# ProtectionChannelC.net
KiCad netlist of a schematic drawn in Altium Designer
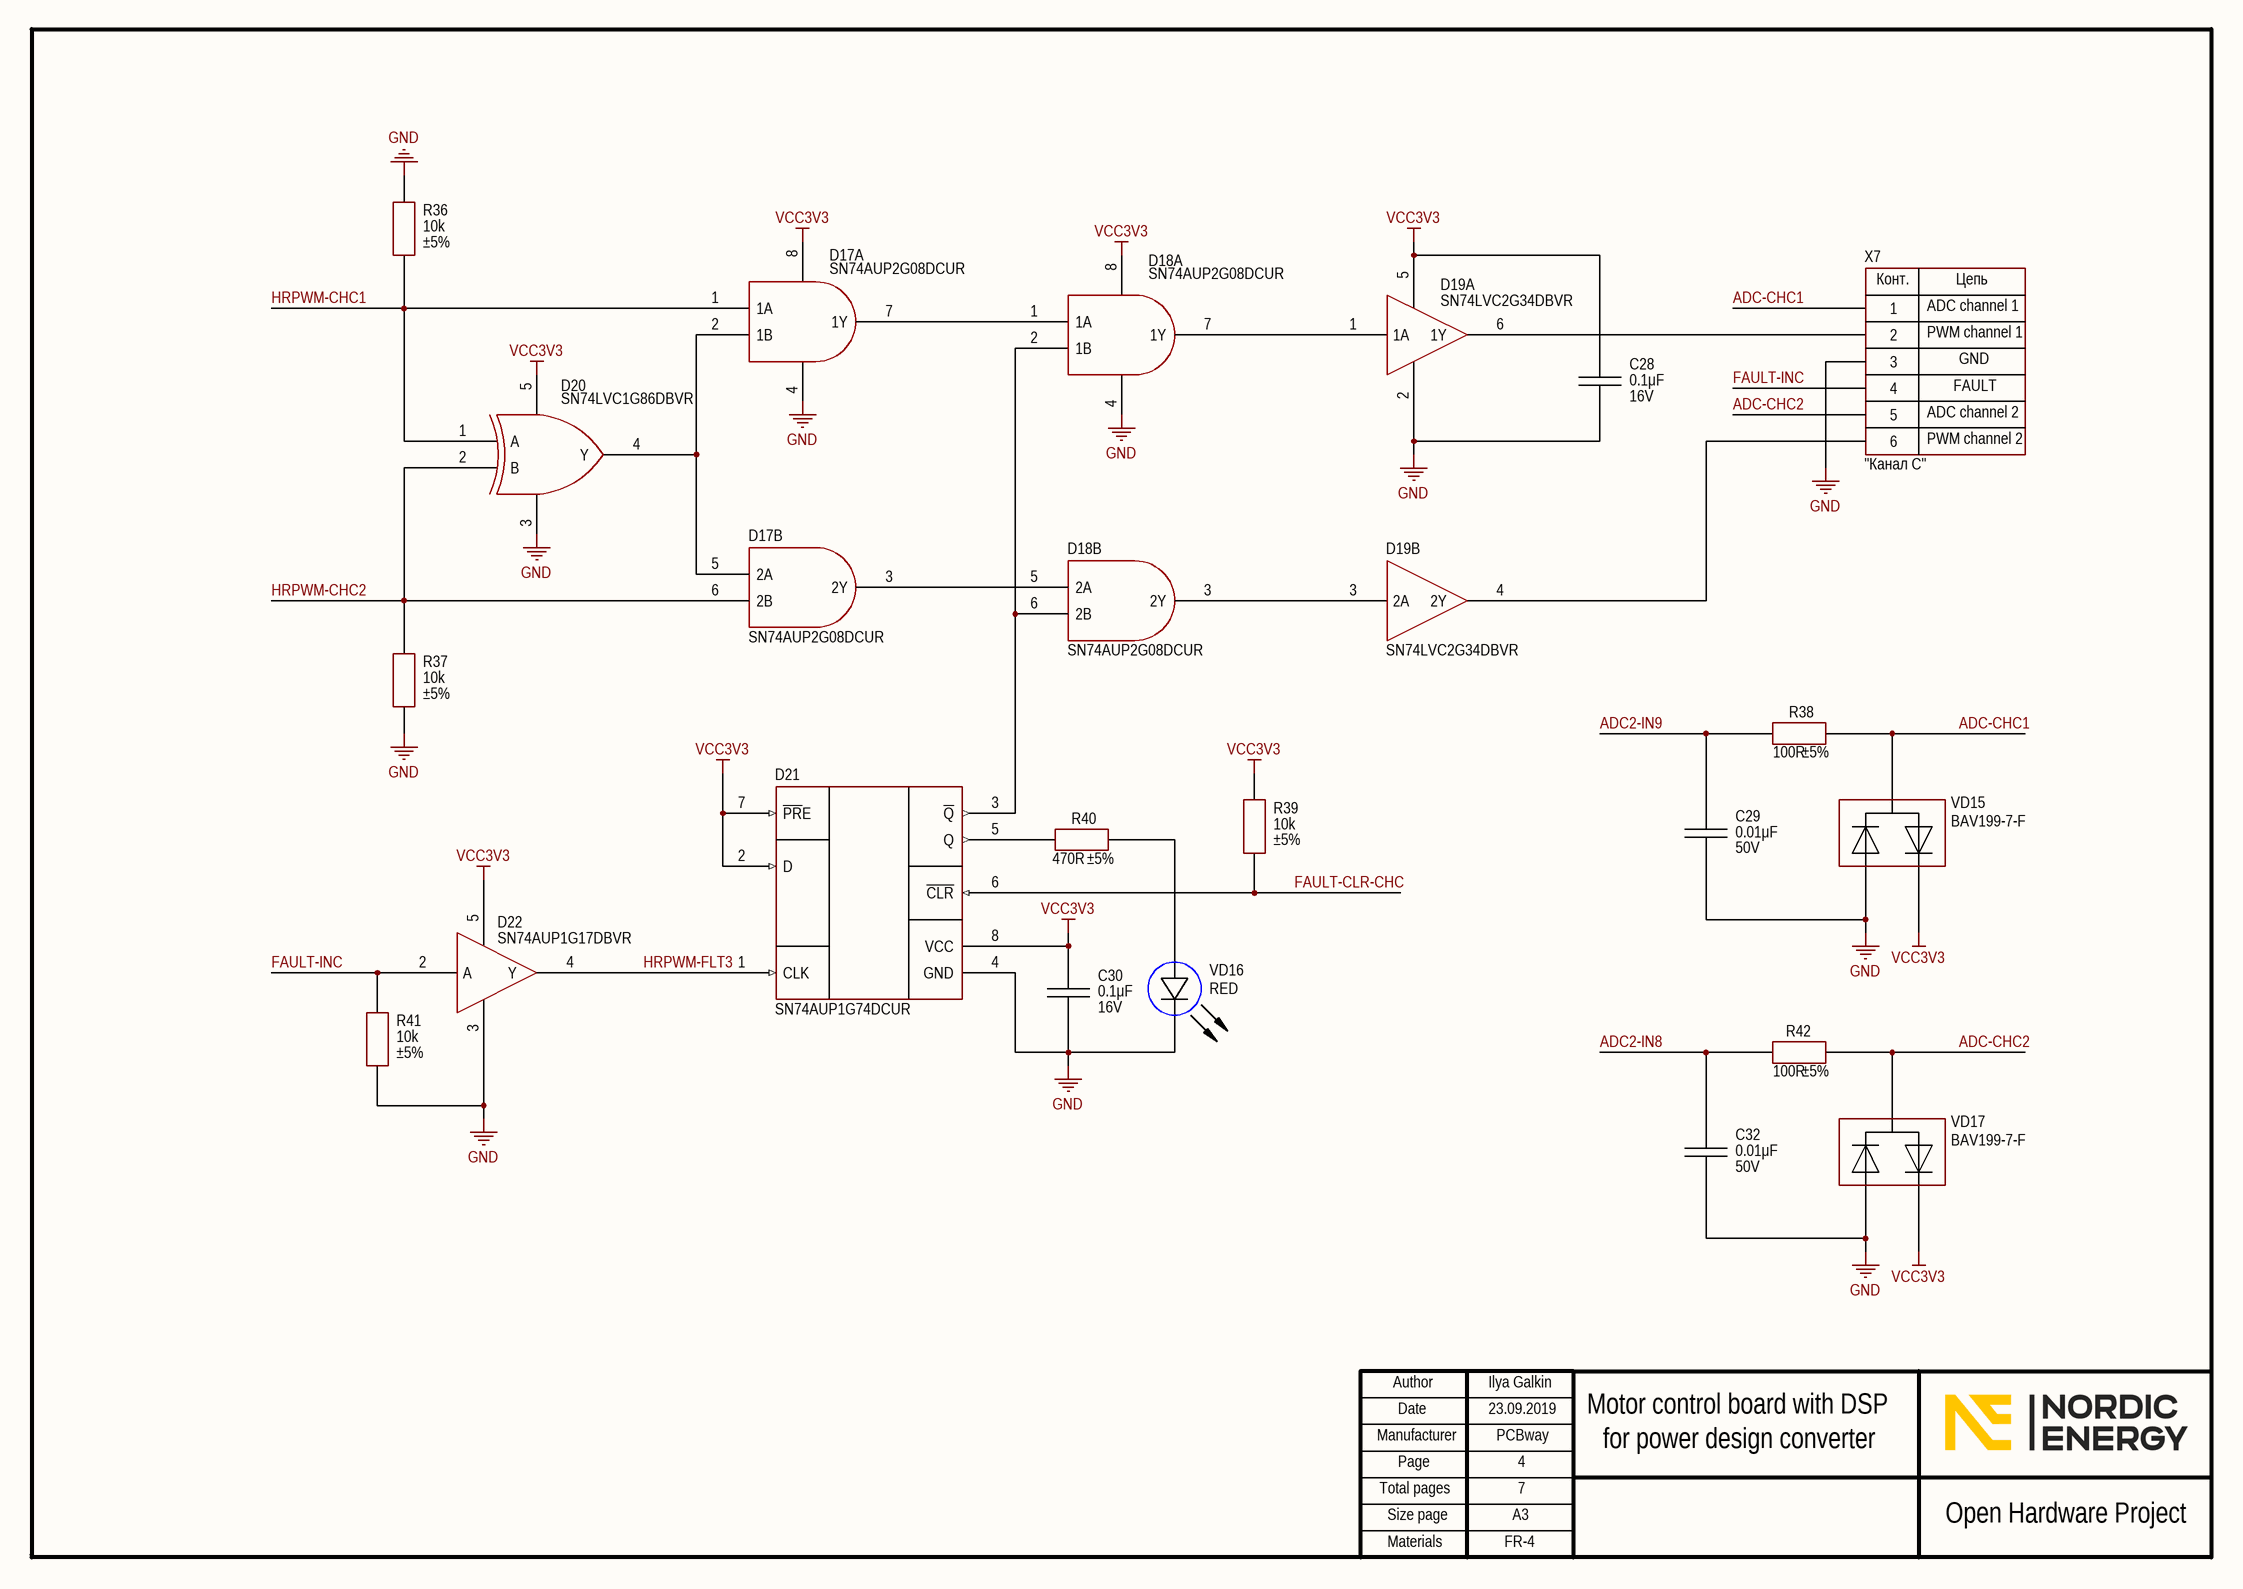
[diagram p0: ProtectionChannelC.SchDoc]

(export (version "E")
  (design (tool "Eeschema 10.0.6"))
  (components
    (comp (ref "C28")
      (value "0.1μF")
      (footprint "CAP: 0805")
      (fields
        (field (name "MANUFACTURER") "Yageo")
        (field (name "PARTNUMBER") "CC0805KRX7R7BB104")
        (field (name "VALUEMANUFACTURERPARTNUMBER") "Ceramic capacitor, 0.1μF, X7R, ±10%, 16V, 0805, -55...+125°C")
        (field (name "VOLTAGE") "16V")
      )
      (libsource (lib "Capacitor") (part "Ceramic_0805"))
    )
    (comp (ref "C29")
      (value "0.01μF")
      (footprint "CAP: 0805")
      (fields
        (field (name "MANUFACTURER") "Yageo")
        (field (name "PARTNUMBER") "CC0805KRX7R9BB103")
        (field (name "VALUEMANUFACTURERPARTNUMBER") "Ceramic capacitor, 0.01μF, X7R, ±10%, 50V, 0805, -55...+125°C")
        (field (name "VOLTAGE") "50V")
      )
      (libsource (lib "Capacitor") (part "Ceramic_0805"))
    )
    (comp (ref "C30")
      (value "0.1μF")
      (footprint "CAP: 0805")
      (fields
        (field (name "MANUFACTURER") "Yageo")
        (field (name "PARTNUMBER") "CC0805KRX7R7BB104")
        (field (name "VALUEMANUFACTURERPARTNUMBER") "Ceramic capacitor, 0.1μF, X7R, ±10%, 16V, 0805, -55...+125°C")
        (field (name "VOLTAGE") "16V")
      )
      (libsource (lib "Capacitor") (part "Ceramic_0805"))
    )
    (comp (ref "C32")
      (value "0.01μF")
      (footprint "CAP: 0805")
      (fields
        (field (name "MANUFACTURER") "Yageo")
        (field (name "PARTNUMBER") "CC0805KRX7R9BB103")
        (field (name "VALUEMANUFACTURERPARTNUMBER") "Ceramic capacitor, 0.01μF, X7R, ±10%, 50V, 0805, -55...+125°C")
        (field (name "VOLTAGE") "50V")
      )
      (libsource (lib "Capacitor") (part "Ceramic_0805"))
    )
    (comp (ref "D17")
      (value "~")
      (footprint "8-VSSOP")
      (description "AND")
      (fields
        (field (name "MANUFACTURER") "Texas Instruments")
        (field (name "VALUEMANUFACTURERPARTNUMBER") "IC logic AND, 0.8...3.6V, -40...+855°C, 8-VSSOP")
        (field (name "PARTNUMBER") "SN74AUP2G08DCUR")
      )
      (libsource (lib "IC. Logic") (part "SN74AUP2G08DCUR"))
    )
    (comp (ref "D18")
      (value "~")
      (footprint "8-VSSOP")
      (description "AND")
      (fields
        (field (name "MANUFACTURER") "Texas Instruments")
        (field (name "VALUEMANUFACTURERPARTNUMBER") "IC logic AND, 0.8...3.6V, -40...+855°C, 8-VSSOP")
        (field (name "PARTNUMBER") "SN74AUP2G08DCUR")
      )
      (libsource (lib "IC. Logic") (part "SN74AUP2G08DCUR"))
    )
    (comp (ref "D19")
      (value "~")
      (footprint "SOT23-6")
      (description "Buffer")
      (fields
        (field (name "MANUFACTURER") "Texas Instruments")
        (field (name "VALUEMANUFACTURERPARTNUMBER") "IC logic buffer, 1.65...5.5V, -40...+125°C, SOT23-6")
        (field (name "PARTNUMBER") "SN74LVC2G34DBVR")
      )
      (libsource (lib "IC. Logic") (part "SN74LVC2G34DBVR"))
    )
    (comp (ref "D20")
      (value "~")
      (footprint "SOT23-5")
      (description "XOR")
      (fields
        (field (name "MANUFACTURER") "Texas Instruments")
        (field (name "VALUEMANUFACTURERPARTNUMBER") "IC logic XOR, 1.65...5.5V, -40...+125°C, SOT23-5")
        (field (name "PARTNUMBER") "SN74LVC1G86DBVR")
      )
      (libsource (lib "IC. Logic") (part "SN74LVC1G86DBVR"))
    )
    (comp (ref "D21")
      (value "~")
      (footprint "8-VSSOP")
      (description "D-trigger")
      (fields
        (field (name "MANUFACTURER") "Texas Instruments")
        (field (name "VALUEMANUFACTURERPARTNUMBER") "ICtrigger D-type, 0.8...3.6V, -40...+85°C, 8-VSSOP")
        (field (name "PARTNUMBER") "SN74AUP1G74DCUR")
      )
      (libsource (lib "IC. Logic") (part "SN74AUP1G74DCUR"))
    )
    (comp (ref "D22")
      (value "~")
      (footprint "SOT23-5")
      (description "Schmitt trigger")
      (fields
        (field (name "MANUFACTURER") "Texas Instruments")
        (field (name "VALUEMANUFACTURERPARTNUMBER") "IC Schmitt trigger, 0.8...3.6V, -40...+85°C, SOT23-6")
        (field (name "PARTNUMBER") "SN74AUP1G17DBVR")
      )
      (libsource (lib "IC. Logic") (part "SN74AUP1G17DBVR"))
    )
    (comp (ref "R36")
      (value "10k")
      (footprint "RES: 0805")
      (fields
        (field (name "MANUFACTURER") "Yageo")
        (field (name "PARTNUMBER") "RC0805JR-0710KL")
        (field (name "VALUEMANUFACTURERPARTNUMBER") "Resistor film, 10k, ±5%, 0805, 0.125W, -55...+125°C")
        (field (name "TOLERANCE") "±5%")
      )
      (libsource (lib "Resistor") (part "Resistor_0805"))
    )
    (comp (ref "R37")
      (value "10k")
      (footprint "RES: 0805")
      (fields
        (field (name "MANUFACTURER") "Yageo")
        (field (name "PARTNUMBER") "RC0805JR-0710KL")
        (field (name "VALUEMANUFACTURERPARTNUMBER") "Resistor film, 10k, ±5%, 0805, 0.125W, -55...+125°C")
        (field (name "TOLERANCE") "±5%")
      )
      (libsource (lib "Resistor") (part "Resistor_0805"))
    )
    (comp (ref "R38")
      (value "100R")
      (footprint "RES: 0805")
      (fields
        (field (name "MANUFACTURER") "Yageo")
        (field (name "PARTNUMBER") "RC0805JR-07100RL")
        (field (name "VALUEMANUFACTURERPARTNUMBER") "Resistor film, 100R, ±5%, 0805, 0.125W, -55...+125°C")
        (field (name "TOLERANCE") "±5%")
      )
      (libsource (lib "") (part "Resistor_0805_1"))
    )
    (comp (ref "R39")
      (value "10k")
      (footprint "RES: 0805")
      (fields
        (field (name "MANUFACTURER") "Yageo")
        (field (name "PARTNUMBER") "RC0805JR-0710KL")
        (field (name "VALUEMANUFACTURERPARTNUMBER") "Resistor film, 10k, ±5%, 0805, 0.125W, -55...+125°C")
        (field (name "TOLERANCE") "±5%")
      )
      (libsource (lib "Resistor") (part "Resistor_0805"))
    )
    (comp (ref "R40")
      (value "470R")
      (footprint "RES: 0805")
      (fields
        (field (name "MANUFACTURER") "Yageo")
        (field (name "PARTNUMBER") "RC0805JR-07470RL")
        (field (name "VALUEMANUFACTURERPARTNUMBER") "Resistor film, 470R, ±5%, 0805, 0.125W, -55...+125°C")
        (field (name "TOLERANCE") "±5%")
      )
      (libsource (lib "") (part "Resistor_0805_2"))
    )
    (comp (ref "R41")
      (value "10k")
      (footprint "RES: 0805")
      (fields
        (field (name "MANUFACTURER") "Yageo")
        (field (name "PARTNUMBER") "RC0805JR-0710KL")
        (field (name "VALUEMANUFACTURERPARTNUMBER") "Resistor film, 10k, ±5%, 0805, 0.125W, -55...+125°C")
        (field (name "TOLERANCE") "±5%")
      )
      (libsource (lib "Resistor") (part "Resistor_0805"))
    )
    (comp (ref "R42")
      (value "100R")
      (footprint "RES: 0805")
      (fields
        (field (name "MANUFACTURER") "Yageo")
        (field (name "PARTNUMBER") "RC0805JR-07100RL")
        (field (name "VALUEMANUFACTURERPARTNUMBER") "Resistor film, 100R, ±5%, 0805, 0.125W, -55...+125°C")
        (field (name "TOLERANCE") "±5%")
      )
      (libsource (lib "") (part "Resistor_0805_1"))
    )
    (comp (ref "VD15")
      (value "~")
      (footprint "SOT23")
      (fields
        (field (name "MANUFACTURER") "Diodes Incorporated")
        (field (name "VALUEMANUFACTURERPARTNUMBER") "Diode array, 85V, 140mA, 1.1V, 3us, SOT-23, -65...+150°C")
        (field (name "VOLTAGE") "85V")
        (field (name "PARTNUMBER") "BAV199-7-F")
      )
      (libsource (lib "Diode") (part "Diode_array"))
    )
    (comp (ref "VD16")
      (value "~")
      (footprint "LED: 0805R")
      (fields
        (field (name "MANUFACTURER") "Wurth")
        (field (name "VALUEMANUFACTURERPARTNUMBER") "LED, 20mA, 2V, 0805, -55...+150°C")
        (field (name "PARTNUMBER") "150080RS75000")
        (field (name "COLOR") "RED")
      )
      (libsource (lib "Diode") (part "LED_single"))
    )
    (comp (ref "VD17")
      (value "~")
      (footprint "SOT23")
      (fields
        (field (name "MANUFACTURER") "Diodes Incorporated")
        (field (name "VALUEMANUFACTURERPARTNUMBER") "Diode array, 85V, 140mA, 1.1V, 3us, SOT-23, -65...+150°C")
        (field (name "VOLTAGE") "85V")
        (field (name "PARTNUMBER") "BAV199-7-F")
      )
      (libsource (lib "Diode") (part "Diode_array"))
    )
    (comp (ref "X7")
      (value "~")
      (footprint "CON: PLD-6")
      (fields
        (field (name "MANUFACTURER") "Connfly")
        (field (name "VALUEMANUFACTURERPARTNUMBER") "Connector, 6pin, 2.54mm, 500VAC, 3A")
        (field (name "PARTNUMBER") "PLD-6")
        (field (name "COMMENTTEXT") "\"Канал C\"")
      )
      (libsource (lib "Connector") (part "PLD-6"))
    )
  )
  (nets
    (net (code "1") (name "/ADC-CHC1") (class "Default")
      (node (ref "R38") (pin "2") (pinfunction "2_2") (pintype "passive"))
      (node (ref "VD15") (pin "3") (pinfunction "3_3") (pintype "passive"))
      (node (ref "X7") (pin "1") (pinfunction "1_1") (pintype "passive"))
    )
    (net (code "2") (name "/ADC-CHC2") (class "Default")
      (node (ref "R42") (pin "2") (pinfunction "2_2") (pintype "passive"))
      (node (ref "VD17") (pin "3") (pinfunction "3_3") (pintype "passive"))
      (node (ref "X7") (pin "5") (pinfunction "5_5") (pintype "power_in"))
    )
    (net (code "3") (name "/ADC2-IN8") (class "Default")
      (node (ref "C32") (pin "2") (pinfunction "2_2") (pintype "power_in"))
      (node (ref "R42") (pin "1") (pinfunction "1_1") (pintype "passive"))
    )
    (net (code "4") (name "/ADC2-IN9") (class "Default")
      (node (ref "C29") (pin "2") (pinfunction "2_2") (pintype "power_in"))
      (node (ref "R38") (pin "1") (pinfunction "1_1") (pintype "passive"))
    )
    (net (code "5") (name "/FAULT-CLR-CHC") (class "Default")
      (node (ref "D21") (pin "6") (pinfunction "~{CLR}_6") (pintype "input"))
      (node (ref "R39") (pin "2") (pinfunction "2_2") (pintype "passive"))
    )
    (net (code "6") (name "/FAULT-INC") (class "Default")
      (node (ref "D22") (pin "2") (pinfunction "A_2") (pintype "passive"))
      (node (ref "R41") (pin "1") (pinfunction "1_1") (pintype "passive"))
      (node (ref "X7") (pin "4") (pinfunction "4_4") (pintype "power_in"))
    )
    (net (code "7") (name "/HRPWM-CHC1") (class "Default")
      (node (ref "D17") (pin "1") (pinfunction "1A_1") (pintype "passive"))
      (node (ref "D20") (pin "1") (pinfunction "A_1") (pintype "passive"))
      (node (ref "R36") (pin "2") (pinfunction "2_2") (pintype "passive"))
    )
    (net (code "8") (name "/HRPWM-CHC2") (class "Default")
      (node (ref "D17") (pin "6") (pinfunction "2B_6") (pintype "passive"))
      (node (ref "D20") (pin "2") (pinfunction "B_2") (pintype "passive"))
      (node (ref "R37") (pin "1") (pinfunction "1_1") (pintype "passive"))
    )
    (net (code "9") (name "/HRPWM-FLT3") (class "Default")
      (node (ref "D21") (pin "1") (pinfunction "CLK_1") (pintype "input"))
      (node (ref "D22") (pin "4") (pinfunction "Y_4") (pintype "passive"))
    )
    (net (code "10") (name "GND") (class "Default")
      (node (ref "C28") (pin "1") (pinfunction "1_1") (pintype "power_in"))
      (node (ref "C29") (pin "1") (pinfunction "1_1") (pintype "power_in"))
      (node (ref "C30") (pin "1") (pinfunction "1_1") (pintype "power_in"))
      (node (ref "C32") (pin "1") (pinfunction "1_1") (pintype "power_in"))
      (node (ref "D17") (pin "4") (pintype "passive"))
      (node (ref "D18") (pin "4") (pintype "passive"))
      (node (ref "D19") (pin "2") (pintype "passive"))
      (node (ref "D20") (pin "3") (pintype "passive"))
      (node (ref "D21") (pin "4") (pinfunction "GND_4") (pintype "passive"))
      (node (ref "D22") (pin "3") (pintype "passive"))
      (node (ref "R36") (pin "1") (pinfunction "1_1") (pintype "passive"))
      (node (ref "R37") (pin "2") (pinfunction "2_2") (pintype "passive"))
      (node (ref "R41") (pin "2") (pinfunction "2_2") (pintype "passive"))
      (node (ref "VD15") (pin "1") (pinfunction "1_1") (pintype "passive"))
      (node (ref "VD16") (pin "2") (pinfunction "C_2") (pintype "passive"))
      (node (ref "VD17") (pin "1") (pinfunction "1_1") (pintype "passive"))
      (node (ref "X7") (pin "3") (pinfunction "3_3") (pintype "power_in"))
    )
    (net (code "11") (name "Net-(D17A-1B)") (class "Default")
      (node (ref "D17") (pin "2") (pinfunction "1B_2") (pintype "passive"))
      (node (ref "D17") (pin "5") (pinfunction "2A_5") (pintype "passive"))
      (node (ref "D20") (pin "4") (pinfunction "Y_4") (pintype "passive"))
    )
    (net (code "12") (name "Net-(D17A-1Y)") (class "Default")
      (node (ref "D17") (pin "7") (pinfunction "1Y_7") (pintype "passive"))
      (node (ref "D18") (pin "1") (pinfunction "1A_1") (pintype "passive"))
    )
    (net (code "13") (name "Net-(D17B-2Y)") (class "Default")
      (node (ref "D17") (pin "3") (pinfunction "2Y_3") (pintype "passive"))
      (node (ref "D18") (pin "5") (pinfunction "2A_5") (pintype "passive"))
    )
    (net (code "14") (name "Net-(D18A-1B)") (class "Default")
      (node (ref "D18") (pin "2") (pinfunction "1B_2") (pintype "passive"))
      (node (ref "D18") (pin "6") (pinfunction "2B_6") (pintype "passive"))
      (node (ref "D21") (pin "3") (pinfunction "~{Q}_3") (pintype "output"))
    )
    (net (code "15") (name "Net-(D18A-1Y)") (class "Default")
      (node (ref "D18") (pin "7") (pinfunction "1Y_7") (pintype "passive"))
      (node (ref "D19") (pin "1") (pinfunction "1A_1") (pintype "passive"))
    )
    (net (code "16") (name "Net-(D18B-2Y)") (class "Default")
      (node (ref "D18") (pin "3") (pinfunction "2Y_3") (pintype "passive"))
      (node (ref "D19") (pin "3") (pinfunction "2A_3") (pintype "passive"))
    )
    (net (code "17") (name "Net-(D19A-1Y)") (class "Default")
      (node (ref "D19") (pin "6") (pinfunction "1Y_6") (pintype "passive"))
      (node (ref "X7") (pin "2") (pinfunction "2_2") (pintype "passive"))
    )
    (net (code "18") (name "Net-(D19B-2Y)") (class "Default")
      (node (ref "D19") (pin "4") (pinfunction "2Y_4") (pintype "passive"))
      (node (ref "X7") (pin "6") (pinfunction "6_6") (pintype "power_in"))
    )
    (net (code "19") (name "Net-(D21-Q)") (class "Default")
      (node (ref "D21") (pin "5") (pinfunction "Q_5") (pintype "output"))
      (node (ref "R40") (pin "2") (pinfunction "2_2") (pintype "passive"))
    )
    (net (code "20") (name "Net-(VD16-A)") (class "Default")
      (node (ref "R40") (pin "1") (pinfunction "1_1") (pintype "passive"))
      (node (ref "VD16") (pin "1") (pinfunction "A_1") (pintype "passive"))
    )
    (net (code "21") (name "VCC3V3") (class "Default")
      (node (ref "C28") (pin "2") (pinfunction "2_2") (pintype "power_in"))
      (node (ref "C30") (pin "2") (pinfunction "2_2") (pintype "power_in"))
      (node (ref "D17") (pin "8") (pintype "passive"))
      (node (ref "D18") (pin "8") (pintype "passive"))
      (node (ref "D19") (pin "5") (pintype "passive"))
      (node (ref "D20") (pin "5") (pintype "passive"))
      (node (ref "D21") (pin "2") (pinfunction "D_2") (pintype "input"))
      (node (ref "D21") (pin "7") (pinfunction "~{PR}E_7") (pintype "input"))
      (node (ref "D21") (pin "8") (pinfunction "VCC_8") (pintype "passive"))
      (node (ref "D22") (pin "5") (pintype "passive"))
      (node (ref "R39") (pin "1") (pinfunction "1_1") (pintype "passive"))
      (node (ref "VD15") (pin "2") (pinfunction "2_2") (pintype "passive"))
      (node (ref "VD17") (pin "2") (pinfunction "2_2") (pintype "passive"))
    )
  )
)
